# Estufa_PIC.net
KiCad netlist of a schematic drawn in EAGLE
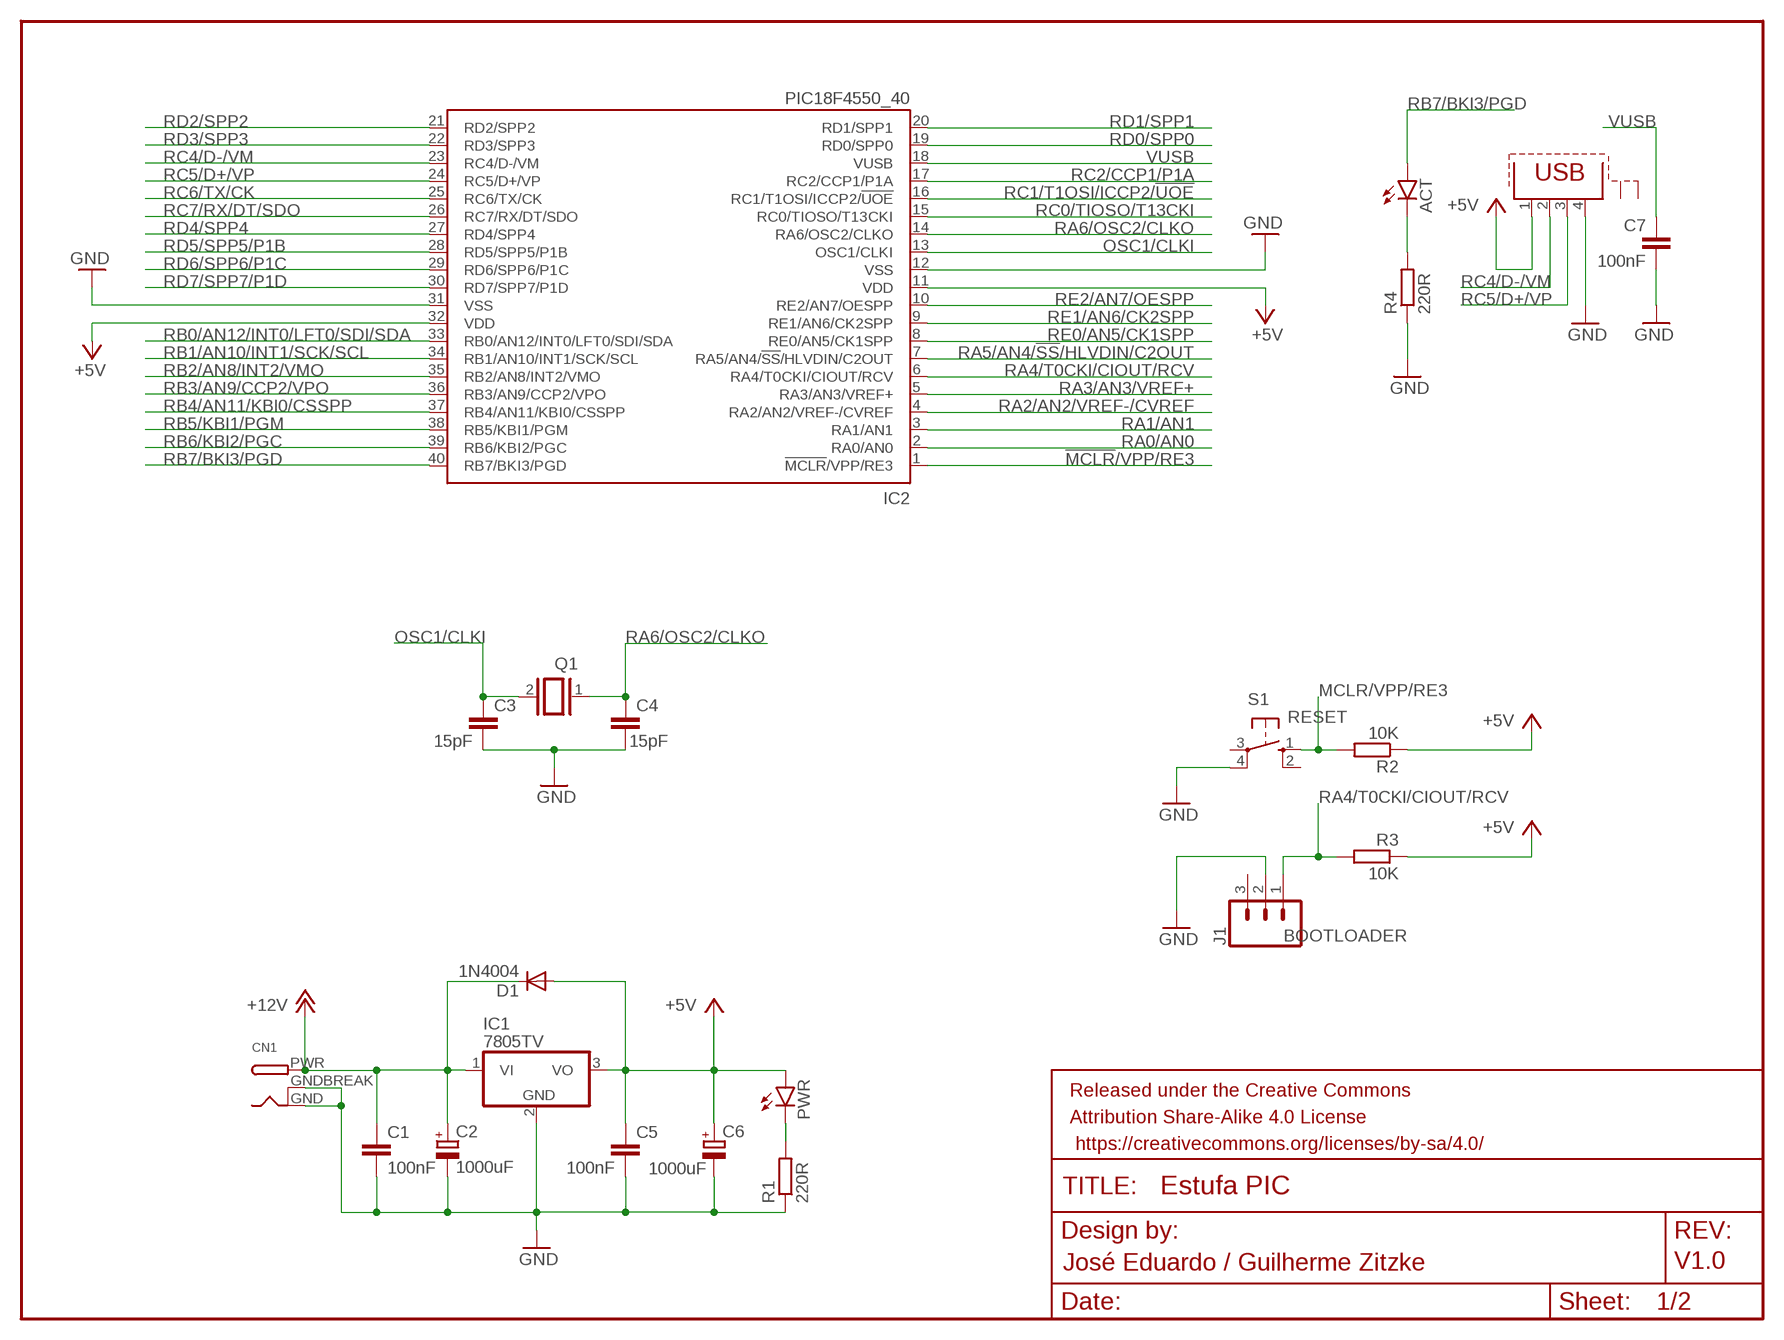
[diagram p0: schematic, sheet 1]
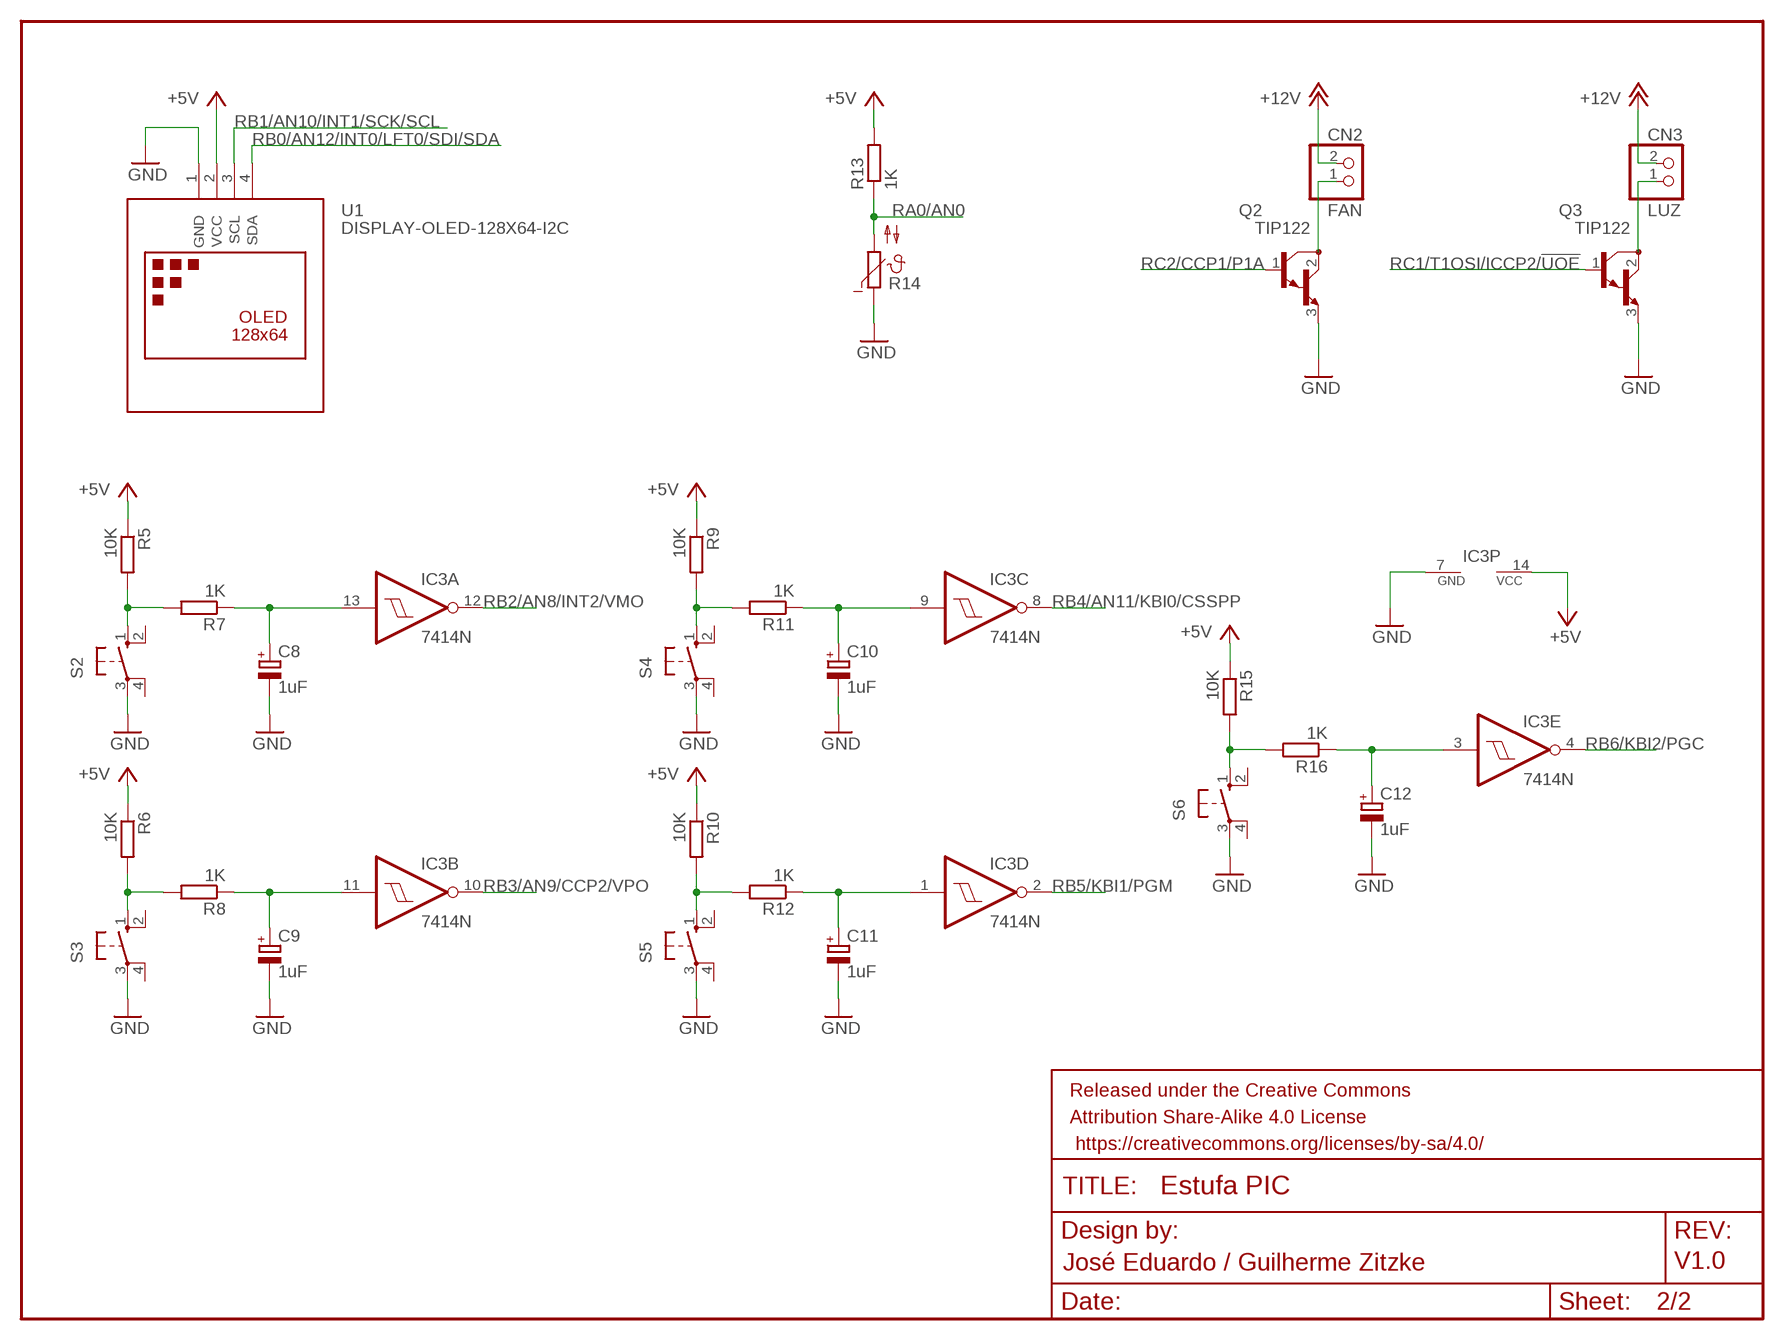
[diagram p1: schematic, sheet 2]

(export (version "E")
  (design (tool "Eeschema 10.0.6"))
  (components
    (comp (ref "ACT")
      (value "LED5MM")
      (footprint "eagle-import:LED5MM")
      (libsource (lib "eagle-import") (part "LED5MM"))
    )
    (comp (ref "C1")
      (value "100nF")
      (footprint "eagle-import:C025-025X050")
      (libsource (lib "eagle-import") (part "C-EU025-025X050"))
    )
    (comp (ref "C2")
      (value "1000uF")
      (footprint "eagle-import:E5-10,5")
      (libsource (lib "eagle-import") (part "CPOL-EUE5-10.5"))
    )
    (comp (ref "C3")
      (value "15pF")
      (footprint "eagle-import:C025-025X050")
      (libsource (lib "eagle-import") (part "C-EU025-025X050"))
    )
    (comp (ref "C4")
      (value "15pF")
      (footprint "eagle-import:C025-025X050")
      (libsource (lib "eagle-import") (part "C-EU025-025X050"))
    )
    (comp (ref "C5")
      (value "100nF")
      (footprint "eagle-import:C025-025X050")
      (libsource (lib "eagle-import") (part "C-EU025-025X050"))
    )
    (comp (ref "C6")
      (value "1000uF")
      (footprint "eagle-import:E5-10,5")
      (libsource (lib "eagle-import") (part "CPOL-EUE5-10.5"))
    )
    (comp (ref "C7")
      (value "100nF")
      (footprint "eagle-import:C025-025X050")
      (libsource (lib "eagle-import") (part "C-EU025-025X050"))
    )
    (comp (ref "CN1")
      (value "DCBARRELPTH")
      (footprint "eagle-import:DCJACK_2MM_PTH")
      (libsource (lib "eagle-import") (part "DCBARRELPTH"))
    )
    (comp (ref "D1")
      (value "1N4004")
      (footprint "eagle-import:DO41-10")
      (libsource (lib "eagle-import") (part "1N4004"))
    )
    (comp (ref "FRAME1")
      (value "FRAME-LETTERNO_PACKAGE")
      (footprint "eagle-import:DUMMY")
      (fields (field (name "DESIGNER") "Nobody"))
      (libsource (lib "eagle-import") (part "FRAME-LETTERNO_PACKAGE"))
    )
    (comp (ref "IC1")
      (value "7805TV")
      (footprint "eagle-import:TO220V")
      (libsource (lib "eagle-import") (part "78TV05"))
    )
    (comp (ref "IC2")
      (value "PIC18F4550_40")
      (footprint "eagle-import:DIL40")
      (fields (field (name "MF") "MICROCHIP") (field (name "MPN") "PIC18F4550-I/P"))
      (libsource (lib "eagle-import") (part "PIC18F4_40550"))
    )
    (comp (ref "J1")
      (value "BOOTLOADER")
      (footprint "eagle-import:1X03_LOCK")
      (libsource (lib "eagle-import") (part "CONN_03LOCK"))
    )
    (comp (ref "PWR")
      (value "LED5MM")
      (footprint "eagle-import:LED5MM")
      (libsource (lib "eagle-import") (part "LED5MM"))
    )
    (comp (ref "Q1")
      (value "XTAL/S")
      (footprint "eagle-import:QS")
      (libsource (lib "eagle-import") (part "XTAL/S"))
    )
    (comp (ref "R1")
      (value "220R")
      (footprint "eagle-import:0207_10")
      (libsource (lib "eagle-import") (part "R-EU_0207/10"))
    )
    (comp (ref "R2")
      (value "10K")
      (footprint "eagle-import:0207_10")
      (libsource (lib "eagle-import") (part "R-EU_0207/10"))
    )
    (comp (ref "R3")
      (value "10K")
      (footprint "eagle-import:0207_10")
      (libsource (lib "eagle-import") (part "R-EU_0207/10"))
    )
    (comp (ref "R4")
      (value "220R")
      (footprint "eagle-import:0207_10")
      (libsource (lib "eagle-import") (part "R-EU_0207/10"))
    )
    (comp (ref "S1")
      (value "RESET")
      (footprint "eagle-import:B3F-40XX")
      (fields (field (name "MF") "OMRON COMPONENTS USA") (field (name "MPN") "B3F-4000"))
      (libsource (lib "eagle-import") (part "40-XX"))
    )
    (comp (ref "X1")
      (value "PN61729-S")
      (footprint "eagle-import:PN61729-S")
      (libsource (lib "eagle-import") (part "PN61729-S"))
    )
    (comp (ref "C8")
      (value "1uF")
      (footprint "eagle-import:E2-5")
      (libsource (lib "eagle-import") (part "CPOL-EUE2-5"))
    )
    (comp (ref "C9")
      (value "1uF")
      (footprint "eagle-import:E2-5")
      (libsource (lib "eagle-import") (part "CPOL-EUE2-5"))
    )
    (comp (ref "C10")
      (value "1uF")
      (footprint "eagle-import:E2-5")
      (libsource (lib "eagle-import") (part "CPOL-EUE2-5"))
    )
    (comp (ref "C11")
      (value "1uF")
      (footprint "eagle-import:E2-5")
      (libsource (lib "eagle-import") (part "CPOL-EUE2-5"))
    )
    (comp (ref "C12")
      (value "1uF")
      (footprint "eagle-import:E2-5")
      (libsource (lib "eagle-import") (part "CPOL-EUE2-5"))
    )
    (comp (ref "CN2")
      (value "FAN")
      (footprint "eagle-import:JST-PH-2-THM")
      (libsource (lib "eagle-import") (part "JST_2PIN-THM"))
    )
    (comp (ref "CN3")
      (value "LUZ")
      (footprint "eagle-import:JST-PH-2-THM")
      (libsource (lib "eagle-import") (part "JST_2PIN-THM"))
    )
    (comp (ref "FRAME2")
      (value "FRAME-LETTERNO_PACKAGE")
      (footprint "eagle-import:DUMMY")
      (fields (field (name "DESIGNER") "Nobody"))
      (libsource (lib "eagle-import") (part "FRAME-LETTERNO_PACKAGE"))
    )
    (comp (ref "IC3")
      (value "7414N")
      (footprint "eagle-import:DIL14")
      (libsource (lib "eagle-import") (part "7414N"))
    )
    (comp (ref "Q2")
      (value "TIP122")
      (footprint "eagle-import:TO220V")
      (libsource (lib "eagle-import") (part "TIP122"))
    )
    (comp (ref "Q3")
      (value "TIP122")
      (footprint "eagle-import:TO220V")
      (libsource (lib "eagle-import") (part "TIP122"))
    )
    (comp (ref "R5")
      (value "10K")
      (footprint "eagle-import:0207_10")
      (libsource (lib "eagle-import") (part "R-EU_0207/10"))
    )
    (comp (ref "R6")
      (value "10K")
      (footprint "eagle-import:0207_10")
      (libsource (lib "eagle-import") (part "R-EU_0207/10"))
    )
    (comp (ref "R7")
      (value "1K")
      (footprint "eagle-import:0207_10")
      (libsource (lib "eagle-import") (part "R-EU_0207/10"))
    )
    (comp (ref "R8")
      (value "1K")
      (footprint "eagle-import:0207_10")
      (libsource (lib "eagle-import") (part "R-EU_0207/10"))
    )
    (comp (ref "R9")
      (value "10K")
      (footprint "eagle-import:0207_10")
      (libsource (lib "eagle-import") (part "R-EU_0207/10"))
    )
    (comp (ref "R10")
      (value "10K")
      (footprint "eagle-import:0207_10")
      (libsource (lib "eagle-import") (part "R-EU_0207/10"))
    )
    (comp (ref "R11")
      (value "1K")
      (footprint "eagle-import:0207_10")
      (libsource (lib "eagle-import") (part "R-EU_0207/10"))
    )
    (comp (ref "R12")
      (value "1K")
      (footprint "eagle-import:0207_10")
      (libsource (lib "eagle-import") (part "R-EU_0207/10"))
    )
    (comp (ref "R13")
      (value "1K")
      (footprint "eagle-import:0207_10")
      (libsource (lib "eagle-import") (part "R-EU_0207/10"))
    )
    (comp (ref "R14")
      (value "NTC644C")
      (footprint "eagle-import:N644C")
      (libsource (lib "eagle-import") (part "NTC644C"))
    )
    (comp (ref "R15")
      (value "10K")
      (footprint "eagle-import:0207_10")
      (libsource (lib "eagle-import") (part "R-EU_0207/10"))
    )
    (comp (ref "R16")
      (value "1K")
      (footprint "eagle-import:0207_10")
      (libsource (lib "eagle-import") (part "R-EU_0207/10"))
    )
    (comp (ref "S2")
      (value "40-XX")
      (footprint "eagle-import:B3F-40XX")
      (fields (field (name "MF") "OMRON COMPONENTS USA") (field (name "MPN") "B3F-4000"))
      (libsource (lib "eagle-import") (part "40-XX"))
    )
    (comp (ref "S3")
      (value "40-XX")
      (footprint "eagle-import:B3F-40XX")
      (fields (field (name "MF") "OMRON COMPONENTS USA") (field (name "MPN") "B3F-4000"))
      (libsource (lib "eagle-import") (part "40-XX"))
    )
    (comp (ref "S4")
      (value "40-XX")
      (footprint "eagle-import:B3F-40XX")
      (fields (field (name "MF") "OMRON COMPONENTS USA") (field (name "MPN") "B3F-4000"))
      (libsource (lib "eagle-import") (part "40-XX"))
    )
    (comp (ref "S5")
      (value "40-XX")
      (footprint "eagle-import:B3F-40XX")
      (fields (field (name "MF") "OMRON COMPONENTS USA") (field (name "MPN") "B3F-4000"))
      (libsource (lib "eagle-import") (part "40-XX"))
    )
    (comp (ref "S6")
      (value "40-XX")
      (footprint "eagle-import:B3F-40XX")
      (fields (field (name "MF") "OMRON COMPONENTS USA") (field (name "MPN") "B3F-4000"))
      (libsource (lib "eagle-import") (part "40-XX"))
    )
    (comp (ref "U1")
      (value "DISPLAY-OLED-128X64-I2C")
      (footprint "eagle-import:DISPLAY-OLED-128X64-I2C")
      (libsource (lib "eagle-import") (part "DISPLAY-OLED-128X64-I2C"))
    )
  )
  (nets
    (net (code "1") (name "+5V") (class "Default")
      (node (ref "C5") (pin "1") (pinfunction "1_1") (pintype "passive"))
      (node (ref "C6") (pin "+") (pinfunction "+_+") (pintype "passive"))
      (node (ref "D1") (pin "A") (pinfunction "A_A") (pintype "passive"))
      (node (ref "IC1") (pin "3") (pinfunction "VO_3") (pintype "passive"))
      (node (ref "IC2") (pin "11") (pinfunction "VDD_11") (pintype "power_in"))
      (node (ref "IC2") (pin "32") (pinfunction "VDD_32") (pintype "power_in"))
      (node (ref "IC3") (pin "14") (pinfunction "VCC_14") (pintype "power_in"))
      (node (ref "PWR") (pin "A") (pinfunction "A_A") (pintype "passive"))
      (node (ref "R10") (pin "1") (pinfunction "1_1") (pintype "passive"))
      (node (ref "R13") (pin "2") (pinfunction "2_2") (pintype "passive"))
      (node (ref "R15") (pin "1") (pinfunction "1_1") (pintype "passive"))
      (node (ref "R2") (pin "1") (pinfunction "1_1") (pintype "passive"))
      (node (ref "R3") (pin "1") (pinfunction "1_1") (pintype "passive"))
      (node (ref "R5") (pin "1") (pinfunction "1_1") (pintype "passive"))
      (node (ref "R6") (pin "1") (pinfunction "1_1") (pintype "passive"))
      (node (ref "R9") (pin "1") (pinfunction "1_1") (pintype "passive"))
      (node (ref "U1") (pin "2") (pinfunction "VCC_2") (pintype "power_in"))
      (node (ref "X1") (pin "1") (pinfunction "1_1") (pintype "passive"))
    )
    (net (code "2") (name "+12V") (class "Default")
      (node (ref "C1") (pin "1") (pinfunction "1_1") (pintype "passive"))
      (node (ref "C2") (pin "+") (pinfunction "+_+") (pintype "passive"))
      (node (ref "CN1") (pin "PWR") (pinfunction "PWR_PWR") (pintype "power_in"))
      (node (ref "CN2") (pin "2") (pinfunction "1_2") (pintype "passive"))
      (node (ref "CN3") (pin "2") (pinfunction "1_2") (pintype "passive"))
      (node (ref "D1") (pin "C") (pinfunction "C_C") (pintype "passive"))
      (node (ref "IC1") (pin "1") (pinfunction "VI_1") (pintype "input"))
    )
    (net (code "3") (name "GND") (class "Default")
      (node (ref "C1") (pin "2") (pinfunction "2_2") (pintype "passive"))
      (node (ref "C10") (pin "-") (pinfunction "-_-") (pintype "passive"))
      (node (ref "C11") (pin "-") (pinfunction "-_-") (pintype "passive"))
      (node (ref "C12") (pin "-") (pinfunction "-_-") (pintype "passive"))
      (node (ref "C2") (pin "-") (pinfunction "-_-") (pintype "passive"))
      (node (ref "C3") (pin "2") (pinfunction "2_2") (pintype "passive"))
      (node (ref "C4") (pin "2") (pinfunction "2_2") (pintype "passive"))
      (node (ref "C5") (pin "2") (pinfunction "2_2") (pintype "passive"))
      (node (ref "C6") (pin "-") (pinfunction "-_-") (pintype "passive"))
      (node (ref "C7") (pin "2") (pinfunction "2_2") (pintype "passive"))
      (node (ref "C8") (pin "-") (pinfunction "-_-") (pintype "passive"))
      (node (ref "C9") (pin "-") (pinfunction "-_-") (pintype "passive"))
      (node (ref "CN1") (pin "GND") (pinfunction "GND_GND") (pintype "power_in"))
      (node (ref "CN1") (pin "GNDBREAK") (pinfunction "GNDBREAK_GNDBREAK") (pintype "power_in"))
      (node (ref "IC1") (pin "2") (pinfunction "GND_2") (pintype "passive"))
      (node (ref "IC2") (pin "12") (pinfunction "VSS_12") (pintype "power_in"))
      (node (ref "IC2") (pin "31") (pinfunction "VSS_31") (pintype "power_in"))
      (node (ref "IC3") (pin "7") (pinfunction "GND_7") (pintype "power_in"))
      (node (ref "J1") (pin "2") (pinfunction "2_2") (pintype "passive"))
      (node (ref "Q2") (pin "3") (pinfunction "E_3") (pintype "passive"))
      (node (ref "Q3") (pin "3") (pinfunction "E_3") (pintype "passive"))
      (node (ref "R1") (pin "1") (pinfunction "1_1") (pintype "passive"))
      (node (ref "R14") (pin "1") (pinfunction "1_1") (pintype "passive"))
      (node (ref "R4") (pin "1") (pinfunction "1_1") (pintype "passive"))
      (node (ref "S1") (pin "4") (pinfunction "P1_4") (pintype "passive"))
      (node (ref "S2") (pin "3") (pinfunction "P_3") (pintype "passive"))
      (node (ref "S3") (pin "3") (pinfunction "P_3") (pintype "passive"))
      (node (ref "S4") (pin "3") (pinfunction "P_3") (pintype "passive"))
      (node (ref "S5") (pin "3") (pinfunction "P_3") (pintype "passive"))
      (node (ref "S6") (pin "3") (pinfunction "P_3") (pintype "passive"))
      (node (ref "U1") (pin "1") (pinfunction "GND_1") (pintype "power_in"))
      (node (ref "X1") (pin "4") (pinfunction "4_4") (pintype "passive"))
    )
    (net (code "4") (name "MCLR{slash}VPP{slash}RE3") (class "Default")
      (node (ref "R2") (pin "2") (pinfunction "2_2") (pintype "passive"))
      (node (ref "S1") (pin "1") (pinfunction "S_1") (pintype "passive"))
    )
    (net (code "5") (name "Net-(ACT-C)") (class "Default")
      (node (ref "ACT") (pin "K") (pinfunction "C_K") (pintype "passive"))
      (node (ref "R4") (pin "2") (pinfunction "2_2") (pintype "passive"))
    )
    (net (code "6") (name "Net-(CN2-2)") (class "Default")
      (node (ref "CN2") (pin "1") (pinfunction "2_1") (pintype "passive"))
      (node (ref "Q2") (pin "2") (pinfunction "C_2") (pintype "passive"))
    )
    (net (code "7") (name "Net-(CN3-2)") (class "Default")
      (node (ref "CN3") (pin "1") (pinfunction "2_1") (pintype "passive"))
      (node (ref "Q3") (pin "2") (pinfunction "C_2") (pintype "passive"))
    )
    (net (code "8") (name "Net-(IC3A-I)") (class "Default")
      (node (ref "C8") (pin "+") (pinfunction "+_+") (pintype "passive"))
      (node (ref "IC3") (pin "13") (pinfunction "I_13") (pintype "input"))
      (node (ref "R7") (pin "1") (pinfunction "1_1") (pintype "passive"))
    )
    (net (code "9") (name "Net-(IC3B-I)") (class "Default")
      (node (ref "C9") (pin "+") (pinfunction "+_+") (pintype "passive"))
      (node (ref "IC3") (pin "11") (pinfunction "I_11") (pintype "input"))
      (node (ref "R8") (pin "1") (pinfunction "1_1") (pintype "passive"))
    )
    (net (code "10") (name "Net-(IC3C-I)") (class "Default")
      (node (ref "C10") (pin "+") (pinfunction "+_+") (pintype "passive"))
      (node (ref "IC3") (pin "9") (pinfunction "I_9") (pintype "input"))
      (node (ref "R11") (pin "1") (pinfunction "1_1") (pintype "passive"))
    )
    (net (code "11") (name "Net-(IC3D-I)") (class "Default")
      (node (ref "C11") (pin "+") (pinfunction "+_+") (pintype "passive"))
      (node (ref "IC3") (pin "1") (pinfunction "I_1") (pintype "input"))
      (node (ref "R12") (pin "1") (pinfunction "1_1") (pintype "passive"))
    )
    (net (code "12") (name "Net-(IC3E-I)") (class "Default")
      (node (ref "C12") (pin "+") (pinfunction "+_+") (pintype "passive"))
      (node (ref "IC3") (pin "3") (pinfunction "I_3") (pintype "input"))
      (node (ref "R16") (pin "1") (pinfunction "1_1") (pintype "passive"))
    )
    (net (code "13") (name "Net-(PWR-C)") (class "Default")
      (node (ref "PWR") (pin "K") (pinfunction "C_K") (pintype "passive"))
      (node (ref "R1") (pin "2") (pinfunction "2_2") (pintype "passive"))
    )
    (net (code "14") (name "Net-(S2-S)") (class "Default")
      (node (ref "R5") (pin "2") (pinfunction "2_2") (pintype "passive"))
      (node (ref "R7") (pin "2") (pinfunction "2_2") (pintype "passive"))
      (node (ref "S2") (pin "1") (pinfunction "S_1") (pintype "passive"))
    )
    (net (code "15") (name "Net-(S3-S)") (class "Default")
      (node (ref "R6") (pin "2") (pinfunction "2_2") (pintype "passive"))
      (node (ref "R8") (pin "2") (pinfunction "2_2") (pintype "passive"))
      (node (ref "S3") (pin "1") (pinfunction "S_1") (pintype "passive"))
    )
    (net (code "16") (name "Net-(S4-S)") (class "Default")
      (node (ref "R11") (pin "2") (pinfunction "2_2") (pintype "passive"))
      (node (ref "R9") (pin "2") (pinfunction "2_2") (pintype "passive"))
      (node (ref "S4") (pin "1") (pinfunction "S_1") (pintype "passive"))
    )
    (net (code "17") (name "Net-(S5-S)") (class "Default")
      (node (ref "R10") (pin "2") (pinfunction "2_2") (pintype "passive"))
      (node (ref "R12") (pin "2") (pinfunction "2_2") (pintype "passive"))
      (node (ref "S5") (pin "1") (pinfunction "S_1") (pintype "passive"))
    )
    (net (code "18") (name "Net-(S6-S)") (class "Default")
      (node (ref "R15") (pin "2") (pinfunction "2_2") (pintype "passive"))
      (node (ref "R16") (pin "2") (pinfunction "2_2") (pintype "passive"))
      (node (ref "S6") (pin "1") (pinfunction "S_1") (pintype "passive"))
    )
    (net (code "19") (name "OSC1{slash}CLKI") (class "Default")
      (node (ref "C3") (pin "1") (pinfunction "1_1") (pintype "passive"))
      (node (ref "IC2") (pin "13") (pinfunction "OSC1/CLKI_13") (pintype "input"))
      (node (ref "Q1") (pin "2") (pinfunction "2_2") (pintype "passive"))
    )
    (net (code "20") (name "RA0{slash}AN0") (class "Default")
      (node (ref "IC2") (pin "2") (pinfunction "RA0/AN0_2") (pintype "bidirectional"))
      (node (ref "R13") (pin "1") (pinfunction "1_1") (pintype "passive"))
      (node (ref "R14") (pin "2") (pinfunction "2_2") (pintype "passive"))
    )
    (net (code "21") (name "RA1{slash}AN1") (class "Default")
      (node (ref "IC2") (pin "3") (pinfunction "RA1/AN1_3") (pintype "bidirectional"))
    )
    (net (code "22") (name "RA2{slash}AN2{slash}VREF-{slash}CVREF") (class "Default")
      (node (ref "IC2") (pin "4") (pinfunction "RA2/AN2/VREF-/CVREF_4") (pintype "bidirectional"))
    )
    (net (code "23") (name "RA3{slash}AN3{slash}VREF+") (class "Default")
      (node (ref "IC2") (pin "5") (pinfunction "RA3/AN3/VREF+_5") (pintype "bidirectional"))
    )
    (net (code "24") (name "RA4{slash}T0CKI{slash}CIOUT{slash}RCV") (class "Default")
      (node (ref "IC2") (pin "6") (pinfunction "RA4/T0CKI/CIOUT/RCV_6") (pintype "bidirectional"))
      (node (ref "J1") (pin "1") (pinfunction "1_1") (pintype "passive"))
      (node (ref "R3") (pin "2") (pinfunction "2_2") (pintype "passive"))
    )
    (net (code "25") (name "RA5{slash}AN4{slash}~{SS}{slash}HLVDIN{slash}C2OUT") (class "Default")
      (node (ref "IC2") (pin "7") (pinfunction "RA5/AN4/~{SS}/HLVDIN/C2OUT_7") (pintype "bidirectional"))
    )
    (net (code "26") (name "RA6{slash}OSC2{slash}CLKO") (class "Default")
      (node (ref "C4") (pin "1") (pinfunction "1_1") (pintype "passive"))
      (node (ref "IC2") (pin "14") (pinfunction "RA6/OSC2/CLKO_14") (pintype "output"))
      (node (ref "Q1") (pin "1") (pinfunction "1_1") (pintype "passive"))
    )
    (net (code "27") (name "RB0{slash}AN12{slash}INT0{slash}LFT0{slash}SDI{slash}SDA") (class "Default")
      (node (ref "IC2") (pin "33") (pinfunction "RB0/AN12/INT0/LFT0/SDI/SDA_33") (pintype "bidirectional"))
      (node (ref "U1") (pin "4") (pinfunction "SDA_4") (pintype "bidirectional"))
    )
    (net (code "28") (name "RB1{slash}AN10{slash}INT1{slash}SCK{slash}SCL") (class "Default")
      (node (ref "IC2") (pin "34") (pinfunction "RB1/AN10/INT1/SCK/SCL_34") (pintype "bidirectional"))
      (node (ref "U1") (pin "3") (pinfunction "SCL_3") (pintype "bidirectional"))
    )
    (net (code "29") (name "RB2{slash}AN8{slash}INT2{slash}VMO") (class "Default")
      (node (ref "IC2") (pin "35") (pinfunction "RB2/AN8/INT2/VMO_35") (pintype "bidirectional"))
      (node (ref "IC3") (pin "12") (pinfunction "O_12") (pintype "output"))
    )
    (net (code "30") (name "RB3{slash}AN9{slash}CCP2{slash}VPO") (class "Default")
      (node (ref "IC2") (pin "36") (pinfunction "RB3/AN9/CCP2/VPO_36") (pintype "bidirectional"))
      (node (ref "IC3") (pin "10") (pinfunction "O_10") (pintype "output"))
    )
    (net (code "31") (name "RB4{slash}AN11{slash}KBI0{slash}CSSPP") (class "Default")
      (node (ref "IC2") (pin "37") (pinfunction "RB4/AN11/KBI0/CSSPP_37") (pintype "bidirectional"))
      (node (ref "IC3") (pin "8") (pinfunction "O_8") (pintype "output"))
    )
    (net (code "32") (name "RB5{slash}KBI1{slash}PGM") (class "Default")
      (node (ref "IC2") (pin "38") (pinfunction "RB5/KBI1/PGM_38") (pintype "bidirectional"))
      (node (ref "IC3") (pin "2") (pinfunction "O_2") (pintype "output"))
    )
    (net (code "33") (name "RB6{slash}KBI2{slash}PGC") (class "Default")
      (node (ref "IC2") (pin "39") (pinfunction "RB6/KBI2/PGC_39") (pintype "bidirectional"))
      (node (ref "IC3") (pin "4") (pinfunction "O_4") (pintype "output"))
    )
    (net (code "34") (name "RB7{slash}BKI3{slash}PGD") (class "Default")
      (node (ref "ACT") (pin "A") (pinfunction "A_A") (pintype "passive"))
      (node (ref "IC2") (pin "40") (pinfunction "RB7/BKI3/PGD_40") (pintype "bidirectional"))
    )
    (net (code "35") (name "RC0{slash}TIOSO{slash}T13CKI") (class "Default")
      (node (ref "IC2") (pin "15") (pinfunction "RC0/TIOSO/T13CKI_15") (pintype "bidirectional"))
    )
    (net (code "36") (name "RC1{slash}T1OSI{slash}ICCP2{slash}~{UOE}") (class "Default")
      (node (ref "IC2") (pin "16") (pinfunction "RC1/T1OSI/ICCP2/~{UOE}_16") (pintype "bidirectional"))
      (node (ref "Q3") (pin "1") (pinfunction "B_1") (pintype "passive"))
    )
    (net (code "37") (name "RC2{slash}CCP1{slash}P1A") (class "Default")
      (node (ref "IC2") (pin "17") (pinfunction "RC2/CCP1/P1A_17") (pintype "bidirectional"))
      (node (ref "Q2") (pin "1") (pinfunction "B_1") (pintype "passive"))
    )
    (net (code "38") (name "RC4{slash}D-{slash}VM") (class "Default")
      (node (ref "IC2") (pin "23") (pinfunction "RC4/D-/VM_23") (pintype "bidirectional"))
      (node (ref "X1") (pin "2") (pinfunction "2_2") (pintype "passive"))
    )
    (net (code "39") (name "RC5{slash}D+{slash}VP") (class "Default")
      (node (ref "IC2") (pin "24") (pinfunction "RC5/D+/VP_24") (pintype "bidirectional"))
      (node (ref "X1") (pin "3") (pinfunction "3_3") (pintype "passive"))
    )
    (net (code "40") (name "RC6{slash}TX{slash}CK") (class "Default")
      (node (ref "IC2") (pin "25") (pinfunction "RC6/TX/CK_25") (pintype "bidirectional"))
    )
    (net (code "41") (name "RC7{slash}RX{slash}DT{slash}SDO") (class "Default")
      (node (ref "IC2") (pin "26") (pinfunction "RC7/RX/DT/SDO_26") (pintype "bidirectional"))
    )
    (net (code "42") (name "RD0{slash}SPP0") (class "Default")
      (node (ref "IC2") (pin "19") (pinfunction "RD0/SPP0_19") (pintype "bidirectional"))
    )
    (net (code "43") (name "RD1{slash}SPP1") (class "Default")
      (node (ref "IC2") (pin "20") (pinfunction "RD1/SPP1_20") (pintype "bidirectional"))
    )
    (net (code "44") (name "RD2{slash}SPP2") (class "Default")
      (node (ref "IC2") (pin "21") (pinfunction "RD2/SPP2_21") (pintype "bidirectional"))
    )
    (net (code "45") (name "RD3{slash}SPP3") (class "Default")
      (node (ref "IC2") (pin "22") (pinfunction "RD3/SPP3_22") (pintype "bidirectional"))
    )
    (net (code "46") (name "RD4{slash}SPP4") (class "Default")
      (node (ref "IC2") (pin "27") (pinfunction "RD4/SPP4_27") (pintype "bidirectional"))
    )
    (net (code "47") (name "RD5{slash}SPP5{slash}P1B") (class "Default")
      (node (ref "IC2") (pin "28") (pinfunction "RD5/SPP5/P1B_28") (pintype "bidirectional"))
    )
    (net (code "48") (name "RD6{slash}SPP6{slash}P1C") (class "Default")
      (node (ref "IC2") (pin "29") (pinfunction "RD6/SPP6/P1C_29") (pintype "bidirectional"))
    )
    (net (code "49") (name "RD7{slash}SPP7{slash}P1D") (class "Default")
      (node (ref "IC2") (pin "30") (pinfunction "RD7/SPP7/P1D_30") (pintype "bidirectional"))
    )
    (net (code "50") (name "RE0{slash}AN5{slash}CK1SPP") (class "Default")
      (node (ref "IC2") (pin "8") (pinfunction "RE0/AN5/CK1SPP_8") (pintype "bidirectional"))
    )
    (net (code "51") (name "RE1{slash}AN6{slash}CK2SPP") (class "Default")
      (node (ref "IC2") (pin "9") (pinfunction "RE1/AN6/CK2SPP_9") (pintype "bidirectional"))
    )
    (net (code "52") (name "RE2{slash}AN7{slash}OESPP") (class "Default")
      (node (ref "IC2") (pin "10") (pinfunction "RE2/AN7/OESPP_10") (pintype "bidirectional"))
    )
    (net (code "53") (name "VUSB") (class "Default")
      (node (ref "C7") (pin "1") (pinfunction "1_1") (pintype "passive"))
      (node (ref "IC2") (pin "18") (pinfunction "VUSB_18") (pintype "bidirectional"))
    )
    (net (code "54") (name "unconnected-(J1-Pad3)") (class "Default")
      (node (ref "J1") (pin "3") (pinfunction "3_3") (pintype "passive"))
    )
    (net (code "55") (name "unconnected-(S1-P-Pad3)") (class "Default")
      (node (ref "S1") (pin "3") (pinfunction "P_3") (pintype "passive"))
    )
    (net (code "56") (name "unconnected-(S1-S1-Pad2)") (class "Default")
      (node (ref "S1") (pin "2") (pinfunction "S1_2") (pintype "passive"))
    )
    (net (code "57") (name "unconnected-(S2-P1-Pad4)") (class "Default")
      (node (ref "S2") (pin "4") (pinfunction "P1_4") (pintype "passive"))
    )
    (net (code "58") (name "unconnected-(S2-S1-Pad2)") (class "Default")
      (node (ref "S2") (pin "2") (pinfunction "S1_2") (pintype "passive"))
    )
    (net (code "59") (name "unconnected-(S3-P1-Pad4)") (class "Default")
      (node (ref "S3") (pin "4") (pinfunction "P1_4") (pintype "passive"))
    )
    (net (code "60") (name "unconnected-(S3-S1-Pad2)") (class "Default")
      (node (ref "S3") (pin "2") (pinfunction "S1_2") (pintype "passive"))
    )
    (net (code "61") (name "unconnected-(S4-P1-Pad4)") (class "Default")
      (node (ref "S4") (pin "4") (pinfunction "P1_4") (pintype "passive"))
    )
    (net (code "62") (name "unconnected-(S4-S1-Pad2)") (class "Default")
      (node (ref "S4") (pin "2") (pinfunction "S1_2") (pintype "passive"))
    )
    (net (code "63") (name "unconnected-(S5-P1-Pad4)") (class "Default")
      (node (ref "S5") (pin "4") (pinfunction "P1_4") (pintype "passive"))
    )
    (net (code "64") (name "unconnected-(S5-S1-Pad2)") (class "Default")
      (node (ref "S5") (pin "2") (pinfunction "S1_2") (pintype "passive"))
    )
    (net (code "65") (name "unconnected-(S6-P1-Pad4)") (class "Default")
      (node (ref "S6") (pin "4") (pinfunction "P1_4") (pintype "passive"))
    )
    (net (code "66") (name "unconnected-(S6-S1-Pad2)") (class "Default")
      (node (ref "S6") (pin "2") (pinfunction "S1_2") (pintype "passive"))
    )
    (net (code "67") (name "unconnected-(X1-PadS1)") (class "Default")
      (node (ref "X1") (pin "S1") (pinfunction "S1_S1") (pintype "passive"))
    )
    (net (code "68") (name "unconnected-(X1-PadS2)") (class "Default")
      (node (ref "X1") (pin "S2") (pinfunction "S2_S2") (pintype "passive"))
    )
    (net (code "69") (name "~{MCLR}{slash}VPP{slash}RE3") (class "Default")
      (node (ref "IC2") (pin "1") (pinfunction "~{MCLR}/VPP/RE3_1") (pintype "input"))
    )
  )
)
